# source_eagle.net
KiCad netlist of a schematic drawn in EAGLE
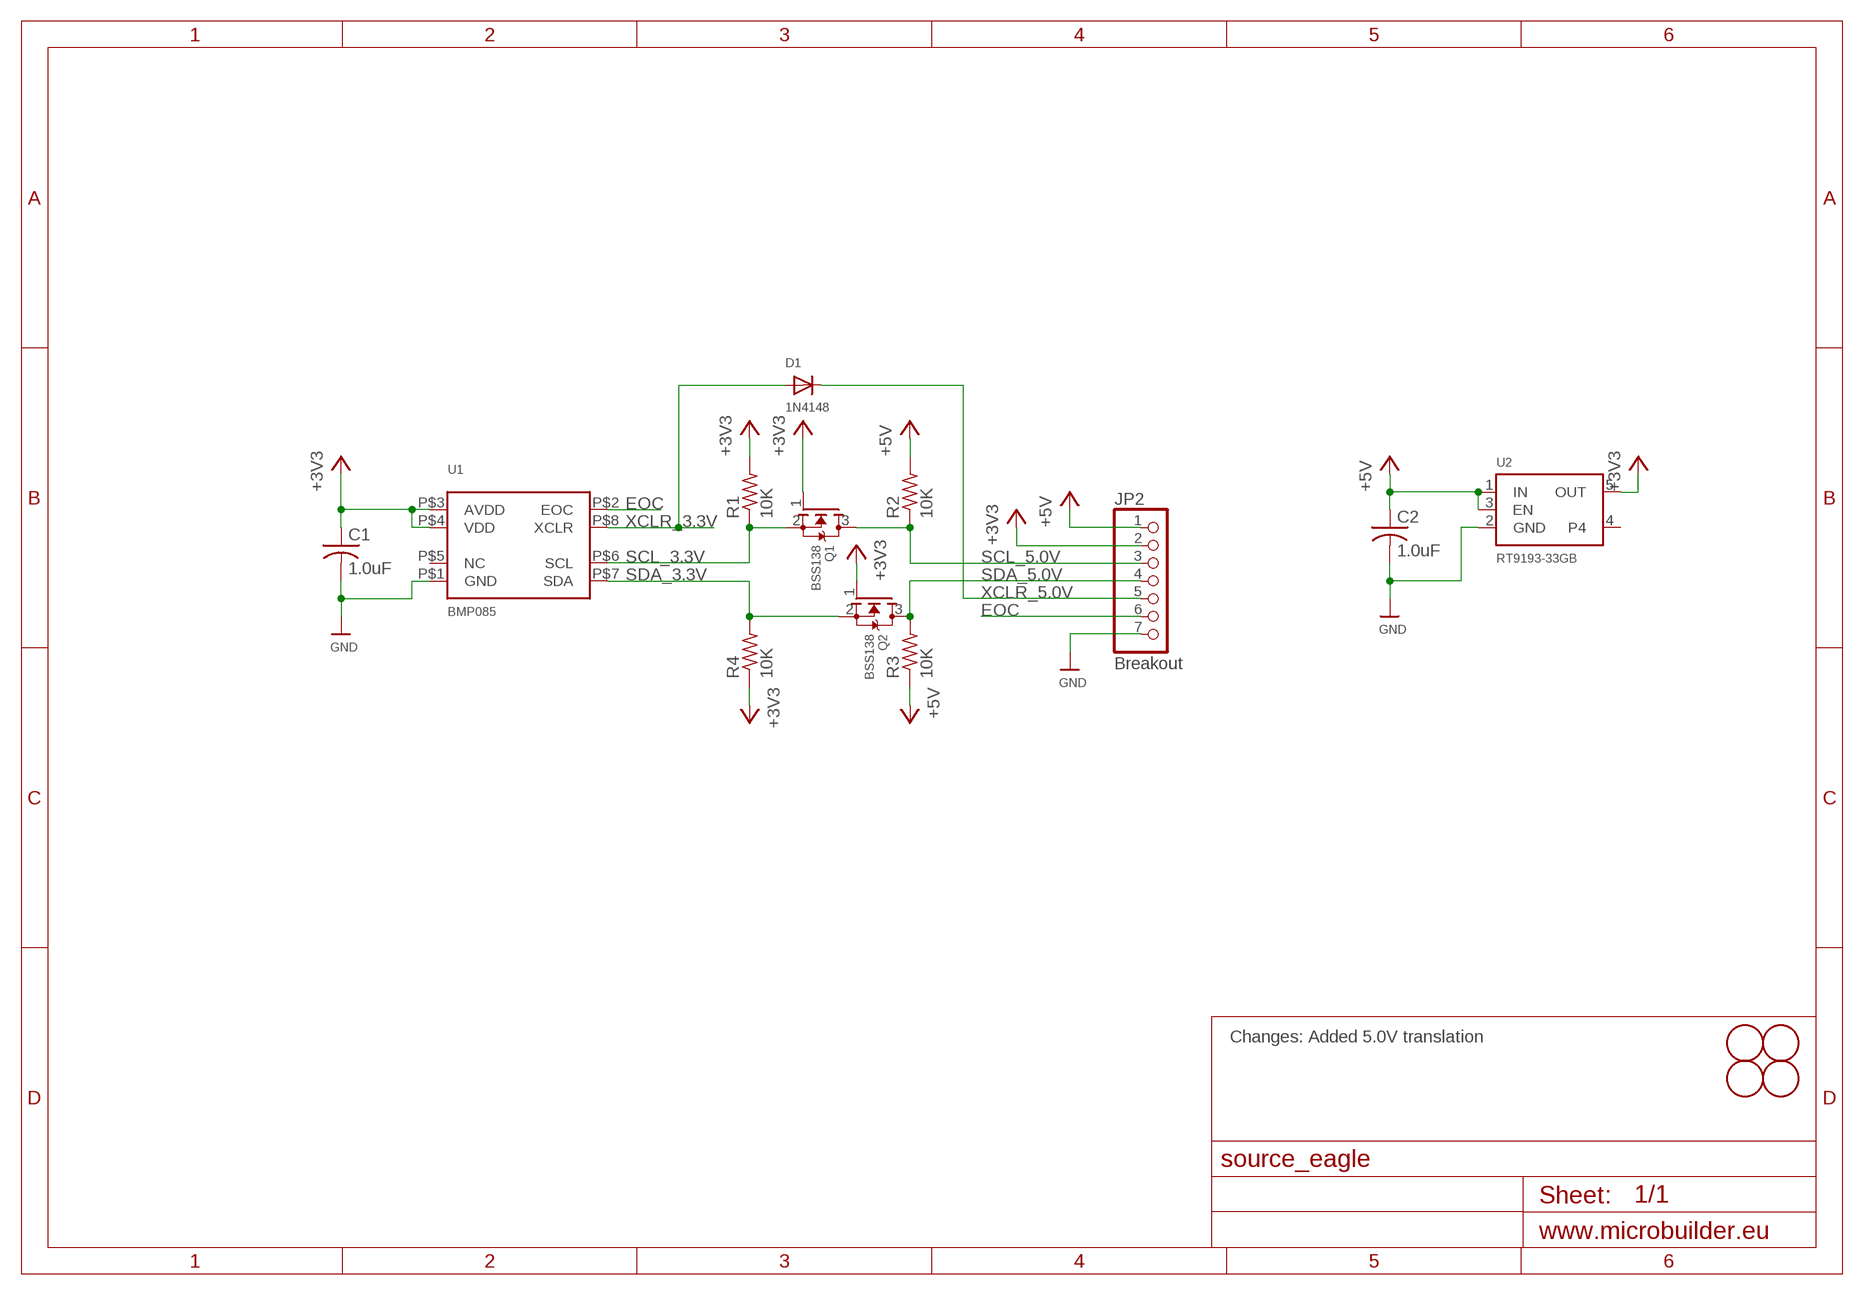
[diagram p0: schematic, sheet 1]

(export (version "E")
  (design (tool "Eeschema 10.0.6"))
  (components
    (comp (ref "C1")
      (value "1.0uF")
      (footprint "eagle-import:C0805")
      (libsource (lib "eagle-import") (part "C-USC0805"))
    )
    (comp (ref "C2")
      (value "1.0uF")
      (footprint "eagle-import:C0805")
      (libsource (lib "eagle-import") (part "C-USC0805"))
    )
    (comp (ref "D1")
      (value "1N4148")
      (footprint "eagle-import:SOD-323F")
      (libsource (lib "eagle-import") (part "DIODESOD-323F"))
    )
    (comp (ref "JP2")
      (value "Breakout")
      (footprint "eagle-import:1X07_ROUND_76")
      (libsource (lib "eagle-import") (part "HEADER-1X7THICKER"))
    )
    (comp (ref "Q1")
      (value "BSS138")
      (footprint "eagle-import:SOT23")
      (libsource (lib "eagle-import") (part "MOSFET-NREFLOW"))
    )
    (comp (ref "Q2")
      (value "BSS138")
      (footprint "eagle-import:SOT23")
      (libsource (lib "eagle-import") (part "MOSFET-NREFLOW"))
    )
    (comp (ref "R1")
      (value "10K")
      (footprint "eagle-import:R0805")
      (libsource (lib "eagle-import") (part "R-US_R0805"))
    )
    (comp (ref "R2")
      (value "10K")
      (footprint "eagle-import:R0805")
      (libsource (lib "eagle-import") (part "R-US_R0805"))
    )
    (comp (ref "R3")
      (value "10K")
      (footprint "eagle-import:R0805")
      (libsource (lib "eagle-import") (part "R-US_R0805"))
    )
    (comp (ref "R4")
      (value "10K")
      (footprint "eagle-import:R0805")
      (libsource (lib "eagle-import") (part "R-US_R0805"))
    )
    (comp (ref "U$1")
      (value "FIDUCIAL")
      (footprint "eagle-import:FIDUCIAL_1MM")
      (libsource (lib "eagle-import") (part "FIDUCIAL"))
    )
    (comp (ref "U$7")
      (value "MOUNTINGHOLE2.0")
      (footprint "eagle-import:MOUNTINGHOLE_2.0_PLATED")
      (libsource (lib "eagle-import") (part "MOUNTINGHOLE2.0"))
    )
    (comp (ref "U$8")
      (value "MOUNTINGHOLE2.0")
      (footprint "eagle-import:MOUNTINGHOLE_2.0_PLATED")
      (libsource (lib "eagle-import") (part "MOUNTINGHOLE2.0"))
    )
    (comp (ref "U$15")
      (value "FIDUCIAL")
      (footprint "eagle-import:FIDUCIAL_1MM")
      (libsource (lib "eagle-import") (part "FIDUCIAL"))
    )
    (comp (ref "U1")
      (value "BMP085")
      (footprint "eagle-import:BMP085")
      (libsource (lib "eagle-import") (part "BMP085"))
    )
    (comp (ref "U2")
      (value "RT9193-33GB")
      (footprint "eagle-import:SOT23-5")
      (libsource (lib "eagle-import") (part "VREG_SOT23-5"))
    )
  )
  (nets
    (net (code "1") (name "+3V3") (class "Default")
      (node (ref "C1") (pin "1") (pinfunction "1_1") (pintype "passive"))
      (node (ref "JP2") (pin "2") (pinfunction "2_2") (pintype "passive"))
      (node (ref "Q1") (pin "1") (pinfunction "G_1") (pintype "bidirectional"))
      (node (ref "Q2") (pin "1") (pinfunction "G_1") (pintype "bidirectional"))
      (node (ref "R1") (pin "2") (pinfunction "2_2") (pintype "passive"))
      (node (ref "R4") (pin "1") (pinfunction "1_1") (pintype "passive"))
      (node (ref "U1") (pin "P$3") (pinfunction "AVDD_P$3") (pintype "bidirectional"))
      (node (ref "U1") (pin "P$4") (pinfunction "VDD_P$4") (pintype "bidirectional"))
      (node (ref "U2") (pin "5") (pinfunction "OUT_5") (pintype "bidirectional"))
    )
    (net (code "2") (name "+5V") (class "Default")
      (node (ref "C2") (pin "1") (pinfunction "1_1") (pintype "passive"))
      (node (ref "JP2") (pin "1") (pinfunction "1_1") (pintype "passive"))
      (node (ref "R2") (pin "2") (pinfunction "2_2") (pintype "passive"))
      (node (ref "R3") (pin "1") (pinfunction "1_1") (pintype "passive"))
      (node (ref "U2") (pin "1") (pinfunction "IN_1") (pintype "bidirectional"))
      (node (ref "U2") (pin "3") (pinfunction "EN_3") (pintype "bidirectional"))
    )
    (net (code "3") (name "/EOC") (class "Default")
      (node (ref "JP2") (pin "6") (pinfunction "6_6") (pintype "passive"))
      (node (ref "U1") (pin "P$2") (pinfunction "EOC_P$2") (pintype "bidirectional"))
    )
    (net (code "4") (name "/SCL_3.3V") (class "Default")
      (node (ref "Q1") (pin "2") (pinfunction "S_2") (pintype "bidirectional"))
      (node (ref "R1") (pin "1") (pinfunction "1_1") (pintype "passive"))
      (node (ref "U1") (pin "P$6") (pinfunction "SCL_P$6") (pintype "bidirectional"))
    )
    (net (code "5") (name "/SCL_5.0V") (class "Default")
      (node (ref "JP2") (pin "3") (pinfunction "3_3") (pintype "passive"))
      (node (ref "Q1") (pin "3") (pinfunction "D_3") (pintype "bidirectional"))
      (node (ref "R2") (pin "1") (pinfunction "1_1") (pintype "passive"))
    )
    (net (code "6") (name "/SDA_3.3V") (class "Default")
      (node (ref "Q2") (pin "2") (pinfunction "S_2") (pintype "bidirectional"))
      (node (ref "R4") (pin "2") (pinfunction "2_2") (pintype "passive"))
      (node (ref "U1") (pin "P$7") (pinfunction "SDA_P$7") (pintype "bidirectional"))
    )
    (net (code "7") (name "/SDA_5.0V") (class "Default")
      (node (ref "JP2") (pin "4") (pinfunction "4_4") (pintype "passive"))
      (node (ref "Q2") (pin "3") (pinfunction "D_3") (pintype "bidirectional"))
      (node (ref "R3") (pin "2") (pinfunction "2_2") (pintype "passive"))
    )
    (net (code "8") (name "/XCLR_3.3V") (class "Default")
      (node (ref "D1") (pin "A") (pinfunction "A_A") (pintype "passive"))
      (node (ref "U1") (pin "P$8") (pinfunction "XCLR_P$8") (pintype "bidirectional"))
    )
    (net (code "9") (name "/XCLR_5.0V") (class "Default")
      (node (ref "D1") (pin "C") (pinfunction "C_C") (pintype "passive"))
      (node (ref "JP2") (pin "5") (pinfunction "5_5") (pintype "passive"))
    )
    (net (code "10") (name "GND") (class "Default")
      (node (ref "C1") (pin "2") (pinfunction "2_2") (pintype "passive"))
      (node (ref "C2") (pin "2") (pinfunction "2_2") (pintype "passive"))
      (node (ref "JP2") (pin "7") (pinfunction "7_7") (pintype "passive"))
      (node (ref "U1") (pin "P$1") (pinfunction "GND_P$1") (pintype "bidirectional"))
      (node (ref "U2") (pin "2") (pinfunction "GND_2") (pintype "bidirectional"))
    )
    (net (code "11") (name "unconnected-(U1-NC-PadP$5)") (class "Default")
      (node (ref "U1") (pin "P$5") (pinfunction "NC_P$5") (pintype "bidirectional"))
    )
    (net (code "12") (name "unconnected-(U2-P4-Pad4)") (class "Default")
      (node (ref "U2") (pin "4") (pinfunction "P4_4") (pintype "bidirectional"))
    )
  )
)
